# USB_MINER_CH340_c2.net
KiCad netlist of a schematic drawn in EAGLE
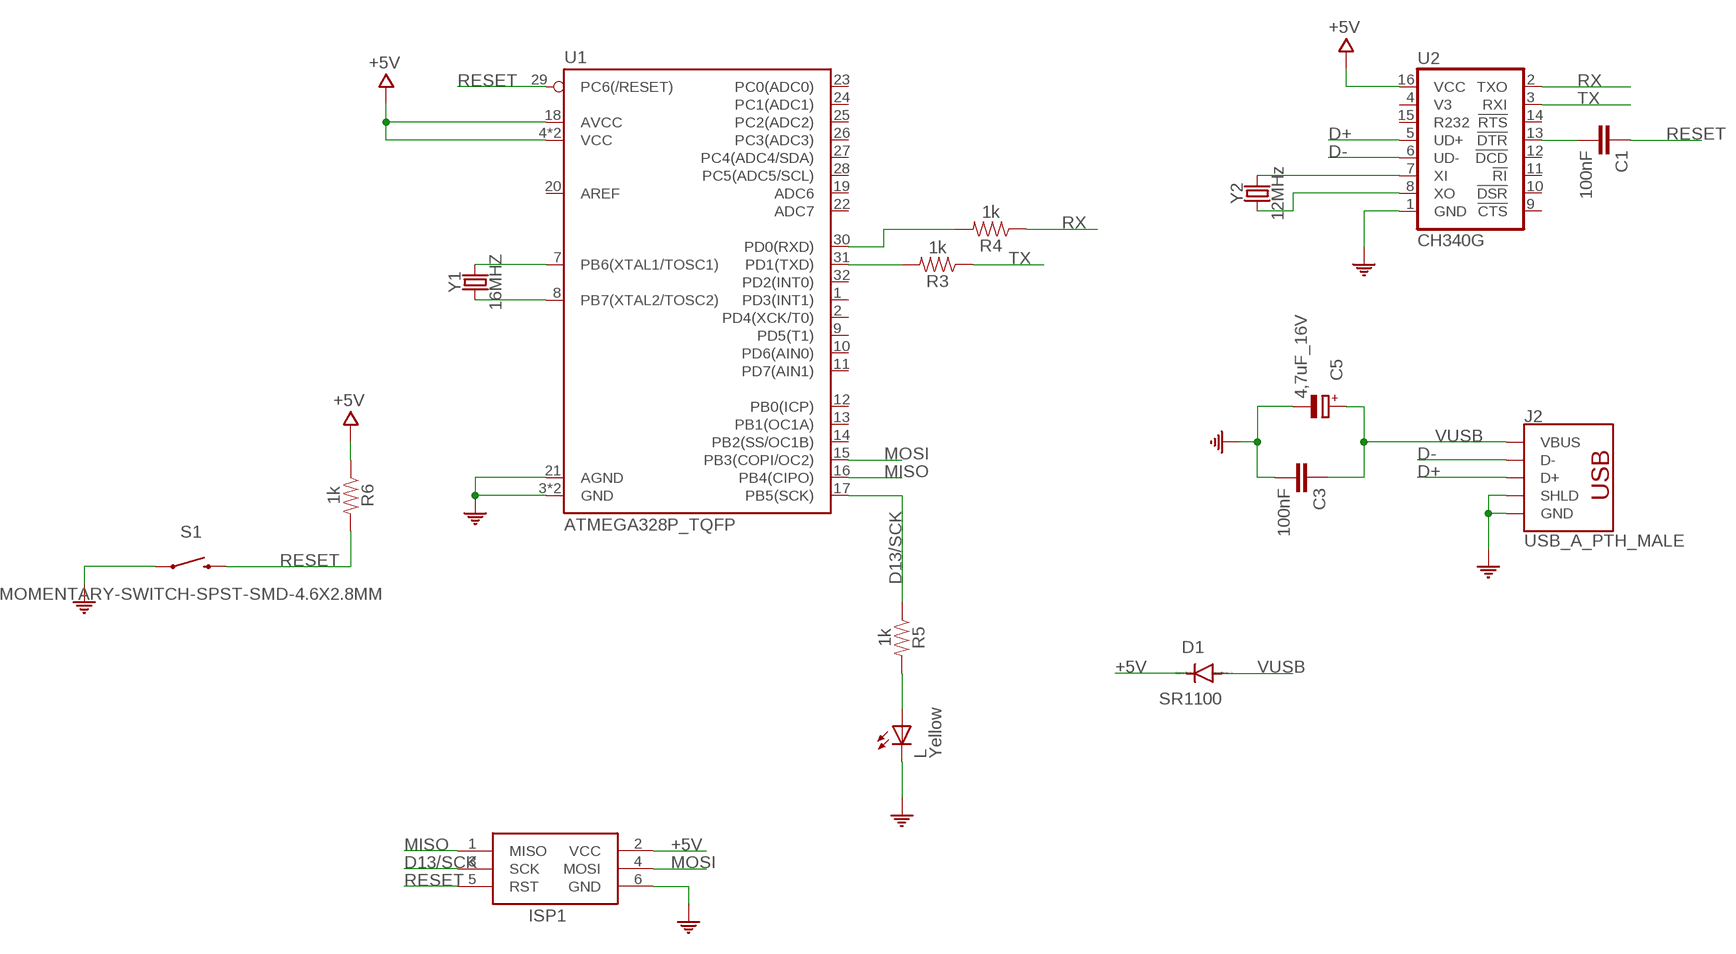
[diagram p0: schematic, sheet 1]

(export (version "E")
  (design (tool "Eeschema 10.0.6"))
  (components
    (comp (ref "C1")
      (value "100nF")
      (footprint "eagle-import:0603")
      (libsource (lib "eagle-import") (part "10NF-0603-50V-10%"))
    )
    (comp (ref "C3")
      (value "100nF")
      (footprint "eagle-import:C0603-ROUND")
      (fields (field (name "PART_NUMBER") "cl10b104kbnc"))
      (libsource (lib "eagle-import") (part "0015_100NF_0603"))
    )
    (comp (ref "C5")
      (value "4,7uF_16V")
      (footprint "eagle-import:TAN-A")
      (fields (field (name "PART_NUMBER") "TAJA475MO16RNJ"))
      (libsource (lib "eagle-import") (part "0833_TAJA475MO16RNJ"))
    )
    (comp (ref "D1")
      (value "SR1100")
      (footprint "eagle-import:DO-214AC")
      (libsource (lib "eagle-import") (part "DIODE-DO-214AC"))
    )
    (comp (ref "ISP1")
      (value "AVRISP-6")
      (footprint "eagle-import:AVRISP")
      (libsource (lib "eagle-import") (part "AVRISP-6"))
    )
    (comp (ref "J2")
      (value "USB_A_PTH_MALE")
      (footprint "eagle-import:USB-A-H")
      (libsource (lib "eagle-import") (part "USB_A_PTH_MALE"))
    )
    (comp (ref "L")
      (value "Yellow")
      (footprint "eagle-import:CHIPLED_0805")
      (fields (field (name "PART_NUMBER") "KPT-2012YC"))
      (libsource (lib "eagle-import") (part "0044_KPT-2012YC"))
    )
    (comp (ref "R3")
      (value "1k")
      (footprint "eagle-import:0603")
      (libsource (lib "eagle-import") (part "1KOHM-0603-1/10W-1%"))
    )
    (comp (ref "R4")
      (value "1k")
      (footprint "eagle-import:0603")
      (libsource (lib "eagle-import") (part "1KOHM-0603-1/10W-1%"))
    )
    (comp (ref "R5")
      (value "1k")
      (footprint "eagle-import:0603")
      (libsource (lib "eagle-import") (part "1KOHM-0603-1/10W-1%"))
    )
    (comp (ref "R6")
      (value "1k")
      (footprint "eagle-import:0603")
      (libsource (lib "eagle-import") (part "1KOHM-0603-1/10W-1%"))
    )
    (comp (ref "S1")
      (value "MOMENTARY-SWITCH-SPST-SMD-4.6X2.8MM")
      (footprint "eagle-import:TACTILE_SWITCH_SMD_4.6X2.8MM")
      (libsource (lib "eagle-import") (part "MOMENTARY-SWITCH-SPST-SMD-4.6X2.8MM"))
    )
    (comp (ref "U1")
      (value "ATMEGA328P_TQFP")
      (footprint "eagle-import:TQFP32-08")
      (libsource (lib "eagle-import") (part "ATMEGA328P_TQFP"))
    )
    (comp (ref "U2")
      (value "CH340G")
      (footprint "eagle-import:SO016")
      (libsource (lib "eagle-import") (part "CH340GSMD"))
    )
    (comp (ref "Y1")
      (value "16MHZ")
      (footprint "eagle-import:HC49UP")
      (libsource (lib "eagle-import") (part "CRYSTALSMD-HC49UP"))
    )
    (comp (ref "Y2")
      (value "12MHz")
      (footprint "eagle-import:HC49UP")
      (libsource (lib "eagle-import") (part "CRYSTALSMD-HC49UP"))
    )
  )
  (nets
    (net (code "1") (name "+5V") (class "Default")
      (node (ref "D1") (pin "C") (pinfunction "C_C") (pintype "passive"))
      (node (ref "ISP1") (pin "2") (pinfunction "VCC_2") (pintype "power_in"))
      (node (ref "R6") (pin "1") (pinfunction "1_1") (pintype "passive"))
      (node (ref "U1") (pin "18") (pinfunction "AVCC_18") (pintype "bidirectional"))
      (node (ref "U1") (pin "4") (pinfunction "VCC_4") (pintype "bidirectional"))
      (node (ref "U1") (pin "6") (pinfunction "VCC_6") (pintype "bidirectional"))
      (node (ref "U2") (pin "16") (pinfunction "VCC_16") (pintype "bidirectional"))
    )
    (net (code "2") (name "/D+") (class "Default")
      (node (ref "J2") (pin "D+") (pinfunction "D+_D+") (pintype "bidirectional"))
      (node (ref "U2") (pin "5") (pinfunction "UD+_5") (pintype "bidirectional"))
    )
    (net (code "3") (name "/D-") (class "Default")
      (node (ref "J2") (pin "D-") (pinfunction "D-_D-") (pintype "bidirectional"))
      (node (ref "U2") (pin "6") (pinfunction "UD-_6") (pintype "bidirectional"))
    )
    (net (code "4") (name "/D13{slash}SCK") (class "Default")
      (node (ref "ISP1") (pin "3") (pinfunction "SCK_3") (pintype "output"))
      (node (ref "R5") (pin "1") (pinfunction "1_1") (pintype "passive"))
      (node (ref "U1") (pin "17") (pinfunction "PB5(SCK)_17") (pintype "bidirectional"))
    )
    (net (code "5") (name "/MISO") (class "Default")
      (node (ref "ISP1") (pin "1") (pinfunction "MISO_1") (pintype "input"))
      (node (ref "U1") (pin "16") (pinfunction "PB4(CIPO)_16") (pintype "bidirectional"))
    )
    (net (code "6") (name "/MOSI") (class "Default")
      (node (ref "ISP1") (pin "4") (pinfunction "MOSI_4") (pintype "output"))
      (node (ref "U1") (pin "15") (pinfunction "PB3(COPI/OC2)_15") (pintype "bidirectional"))
    )
    (net (code "7") (name "/RESET") (class "Default")
      (node (ref "C1") (pin "1") (pinfunction "1_1") (pintype "passive"))
      (node (ref "ISP1") (pin "5") (pinfunction "RST_5") (pintype "output"))
      (node (ref "R6") (pin "2") (pinfunction "2_2") (pintype "passive"))
      (node (ref "S1") (pin "3") (pinfunction "2_3") (pintype "passive"))
      (node (ref "S1") (pin "4") (pinfunction "2_4") (pintype "passive"))
      (node (ref "U1") (pin "29") (pinfunction "PC6(/RESET)_29") (pintype "bidirectional"))
    )
    (net (code "8") (name "/RX") (class "Default")
      (node (ref "R4") (pin "1") (pinfunction "1_1") (pintype "passive"))
      (node (ref "U2") (pin "2") (pinfunction "TXO_2") (pintype "bidirectional"))
    )
    (net (code "9") (name "/TX") (class "Default")
      (node (ref "R3") (pin "1") (pinfunction "1_1") (pintype "passive"))
      (node (ref "U2") (pin "3") (pinfunction "RXI_3") (pintype "bidirectional"))
    )
    (net (code "10") (name "/VUSB") (class "Default")
      (node (ref "C3") (pin "1") (pinfunction "1_1") (pintype "passive"))
      (node (ref "C5") (pin "1") (pinfunction "+_1") (pintype "passive"))
      (node (ref "D1") (pin "A") (pinfunction "A_A") (pintype "passive"))
      (node (ref "J2") (pin "VBUS") (pinfunction "VBUS_VBUS") (pintype "power_in"))
    )
    (net (code "11") (name "COM") (class "Default")
      (node (ref "C3") (pin "2") (pinfunction "2_2") (pintype "passive"))
      (node (ref "C5") (pin "2") (pinfunction "-_2") (pintype "passive"))
      (node (ref "ISP1") (pin "6") (pinfunction "GND_6") (pintype "power_in"))
      (node (ref "J2") (pin "GND") (pinfunction "GND_GND") (pintype "power_in"))
      (node (ref "J2") (pin "SHLD1") (pinfunction "SHLD_SHLD1") (pintype "bidirectional"))
      (node (ref "J2") (pin "SHLD2") (pinfunction "SHLD_SHLD2") (pintype "bidirectional"))
      (node (ref "L") (pin "C") (pinfunction "C_C") (pintype "passive"))
      (node (ref "S1") (pin "1") (pinfunction "1_1") (pintype "passive"))
      (node (ref "S1") (pin "2") (pinfunction "1_2") (pintype "passive"))
      (node (ref "U1") (pin "21") (pinfunction "AGND_21") (pintype "bidirectional"))
      (node (ref "U1") (pin "3") (pinfunction "GND_3") (pintype "bidirectional"))
      (node (ref "U1") (pin "5") (pinfunction "GND_5") (pintype "bidirectional"))
      (node (ref "U2") (pin "1") (pinfunction "GND_1") (pintype "bidirectional"))
    )
    (net (code "12") (name "Net-(L-PadA)") (class "Default")
      (node (ref "L") (pin "A") (pinfunction "A_A") (pintype "passive"))
      (node (ref "R5") (pin "2") (pinfunction "2_2") (pintype "passive"))
    )
    (net (code "13") (name "Net-(U1-PB6(XTAL1{slash}TOSC1))") (class "Default")
      (node (ref "U1") (pin "7") (pinfunction "PB6(XTAL1/TOSC1)_7") (pintype "bidirectional"))
      (node (ref "Y1") (pin "2") (pinfunction "2_2") (pintype "passive"))
    )
    (net (code "14") (name "Net-(U1-PB7(XTAL2{slash}TOSC2))") (class "Default")
      (node (ref "U1") (pin "8") (pinfunction "PB7(XTAL2/TOSC2)_8") (pintype "bidirectional"))
      (node (ref "Y1") (pin "1") (pinfunction "1_1") (pintype "passive"))
    )
    (net (code "15") (name "Net-(U1-PD0(RXD))") (class "Default")
      (node (ref "R4") (pin "2") (pinfunction "2_2") (pintype "passive"))
      (node (ref "U1") (pin "30") (pinfunction "PD0(RXD)_30") (pintype "bidirectional"))
    )
    (net (code "16") (name "Net-(U1-PD1(TXD))") (class "Default")
      (node (ref "R3") (pin "2") (pinfunction "2_2") (pintype "passive"))
      (node (ref "U1") (pin "31") (pinfunction "PD1(TXD)_31") (pintype "bidirectional"))
    )
    (net (code "17") (name "Net-(U2-XI)") (class "Default")
      (node (ref "U2") (pin "7") (pinfunction "XI_7") (pintype "bidirectional"))
      (node (ref "Y2") (pin "2") (pinfunction "2_2") (pintype "passive"))
    )
    (net (code "18") (name "Net-(U2-XO)") (class "Default")
      (node (ref "U2") (pin "8") (pinfunction "XO_8") (pintype "bidirectional"))
      (node (ref "Y2") (pin "1") (pinfunction "1_1") (pintype "passive"))
    )
    (net (code "19") (name "Net-(U2-~{DTR})") (class "Default")
      (node (ref "C1") (pin "2") (pinfunction "2_2") (pintype "passive"))
      (node (ref "U2") (pin "13") (pinfunction "~{DTR}_13") (pintype "bidirectional"))
    )
    (net (code "20") (name "unconnected-(U1-ADC6-Pad19)") (class "Default")
      (node (ref "U1") (pin "19") (pinfunction "ADC6_19") (pintype "bidirectional"))
    )
    (net (code "21") (name "unconnected-(U1-ADC7-Pad22)") (class "Default")
      (node (ref "U1") (pin "22") (pinfunction "ADC7_22") (pintype "bidirectional"))
    )
    (net (code "22") (name "unconnected-(U1-AREF-Pad20)") (class "Default")
      (node (ref "U1") (pin "20") (pinfunction "AREF_20") (pintype "bidirectional"))
    )
    (net (code "23") (name "unconnected-(U1-PB0(ICP)-Pad12)") (class "Default")
      (node (ref "U1") (pin "12") (pinfunction "PB0(ICP)_12") (pintype "bidirectional"))
    )
    (net (code "24") (name "unconnected-(U1-PB1(OC1A)-Pad13)") (class "Default")
      (node (ref "U1") (pin "13") (pinfunction "PB1(OC1A)_13") (pintype "bidirectional"))
    )
    (net (code "25") (name "unconnected-(U1-PB2(SS{slash}OC1B)-Pad14)") (class "Default")
      (node (ref "U1") (pin "14") (pinfunction "PB2(SS/OC1B)_14") (pintype "bidirectional"))
    )
    (net (code "26") (name "unconnected-(U1-PC0(ADC0)-Pad23)") (class "Default")
      (node (ref "U1") (pin "23") (pinfunction "PC0(ADC0)_23") (pintype "bidirectional"))
    )
    (net (code "27") (name "unconnected-(U1-PC1(ADC1)-Pad24)") (class "Default")
      (node (ref "U1") (pin "24") (pinfunction "PC1(ADC1)_24") (pintype "bidirectional"))
    )
    (net (code "28") (name "unconnected-(U1-PC2(ADC2)-Pad25)") (class "Default")
      (node (ref "U1") (pin "25") (pinfunction "PC2(ADC2)_25") (pintype "bidirectional"))
    )
    (net (code "29") (name "unconnected-(U1-PC3(ADC3)-Pad26)") (class "Default")
      (node (ref "U1") (pin "26") (pinfunction "PC3(ADC3)_26") (pintype "bidirectional"))
    )
    (net (code "30") (name "unconnected-(U1-PC4(ADC4{slash}SDA)-Pad27)") (class "Default")
      (node (ref "U1") (pin "27") (pinfunction "PC4(ADC4/SDA)_27") (pintype "bidirectional"))
    )
    (net (code "31") (name "unconnected-(U1-PC5(ADC5{slash}SCL)-Pad28)") (class "Default")
      (node (ref "U1") (pin "28") (pinfunction "PC5(ADC5/SCL)_28") (pintype "bidirectional"))
    )
    (net (code "32") (name "unconnected-(U1-PD2(INT0)-Pad32)") (class "Default")
      (node (ref "U1") (pin "32") (pinfunction "PD2(INT0)_32") (pintype "bidirectional"))
    )
    (net (code "33") (name "unconnected-(U1-PD3(INT1)-Pad1)") (class "Default")
      (node (ref "U1") (pin "1") (pinfunction "PD3(INT1)_1") (pintype "bidirectional"))
    )
    (net (code "34") (name "unconnected-(U1-PD4(XCK{slash}T0)-Pad2)") (class "Default")
      (node (ref "U1") (pin "2") (pinfunction "PD4(XCK/T0)_2") (pintype "bidirectional"))
    )
    (net (code "35") (name "unconnected-(U1-PD5(T1)-Pad9)") (class "Default")
      (node (ref "U1") (pin "9") (pinfunction "PD5(T1)_9") (pintype "bidirectional"))
    )
    (net (code "36") (name "unconnected-(U1-PD6(AIN0)-Pad10)") (class "Default")
      (node (ref "U1") (pin "10") (pinfunction "PD6(AIN0)_10") (pintype "bidirectional"))
    )
    (net (code "37") (name "unconnected-(U1-PD7(AIN1)-Pad11)") (class "Default")
      (node (ref "U1") (pin "11") (pinfunction "PD7(AIN1)_11") (pintype "bidirectional"))
    )
    (net (code "38") (name "unconnected-(U2-R232-Pad15)") (class "Default")
      (node (ref "U2") (pin "15") (pinfunction "R232_15") (pintype "bidirectional"))
    )
    (net (code "39") (name "unconnected-(U2-V3-Pad4)") (class "Default")
      (node (ref "U2") (pin "4") (pinfunction "V3_4") (pintype "bidirectional"))
    )
    (net (code "40") (name "unconnected-(U2-~{CTS}-Pad9)") (class "Default")
      (node (ref "U2") (pin "9") (pinfunction "~{CTS}_9") (pintype "bidirectional"))
    )
    (net (code "41") (name "unconnected-(U2-~{DCD}-Pad12)") (class "Default")
      (node (ref "U2") (pin "12") (pinfunction "~{DCD}_12") (pintype "bidirectional"))
    )
    (net (code "42") (name "unconnected-(U2-~{DSR}-Pad10)") (class "Default")
      (node (ref "U2") (pin "10") (pinfunction "~{DSR}_10") (pintype "bidirectional"))
    )
    (net (code "43") (name "unconnected-(U2-~{RI}-Pad11)") (class "Default")
      (node (ref "U2") (pin "11") (pinfunction "~{RI}_11") (pintype "bidirectional"))
    )
    (net (code "44") (name "unconnected-(U2-~{RTS}-Pad14)") (class "Default")
      (node (ref "U2") (pin "14") (pinfunction "~{RTS}_14") (pintype "bidirectional"))
    )
  )
)
